# displayplank.net
KiCad netlist of a schematic drawn in EAGLE
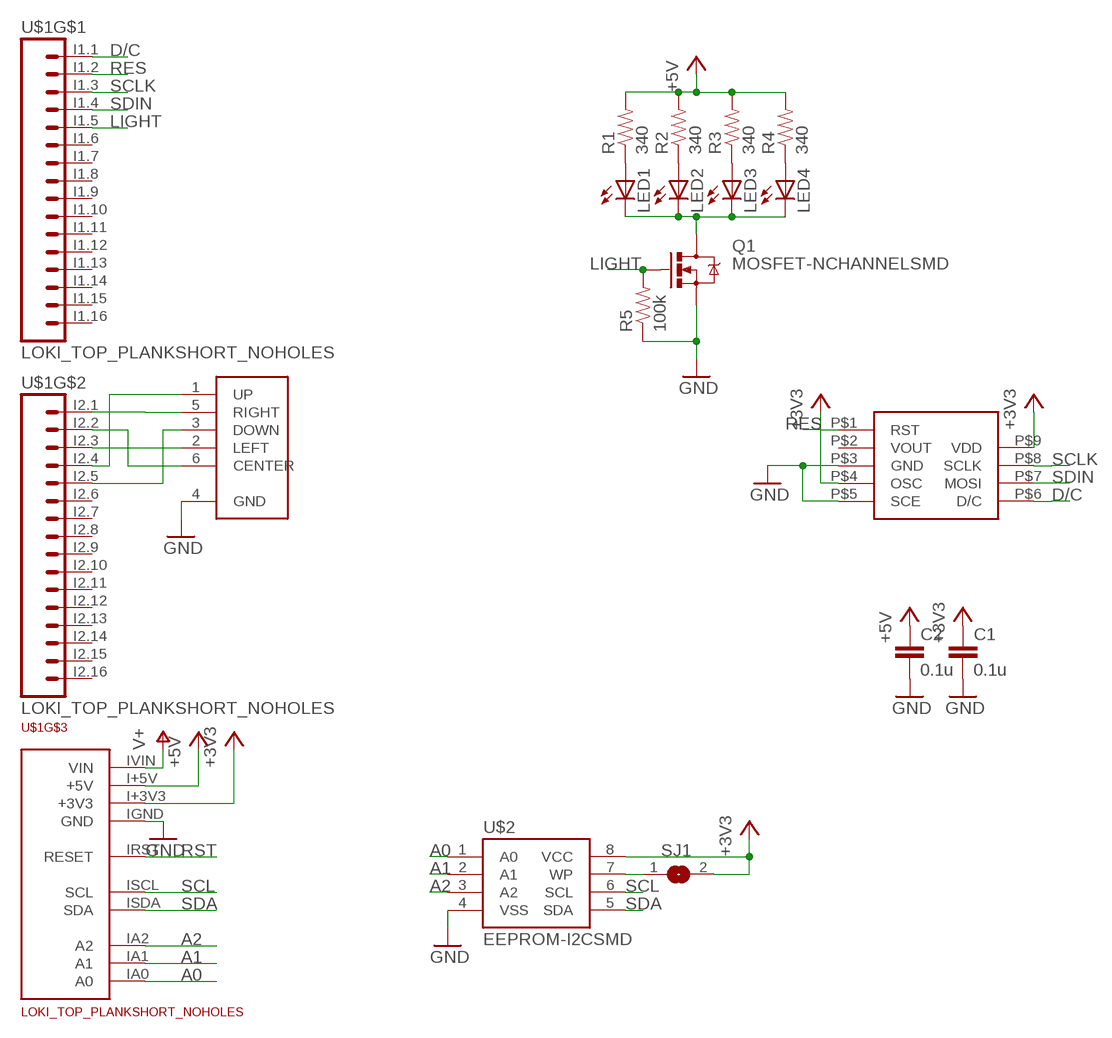
[diagram p0: schematic, sheet 1]

(export (version "E")
  (design (tool "Eeschema 10.0.6"))
  (components
    (comp (ref "C1")
      (value "0.1u")
      (footprint "eagle-import:0805")
      (libsource (lib "eagle-import") (part "CAP0805"))
    )
    (comp (ref "C2")
      (value "0.1u")
      (footprint "eagle-import:0805")
      (libsource (lib "eagle-import") (part "CAP0805"))
    )
    (comp (ref "LED1")
      (value "LEDSML0805")
      (footprint "eagle-import:SML0805")
      (libsource (lib "eagle-import") (part "LEDSML0805"))
    )
    (comp (ref "LED2")
      (value "LEDSML0805")
      (footprint "eagle-import:SML0805")
      (libsource (lib "eagle-import") (part "LEDSML0805"))
    )
    (comp (ref "LED3")
      (value "LEDSML0805")
      (footprint "eagle-import:SML0805")
      (libsource (lib "eagle-import") (part "LEDSML0805"))
    )
    (comp (ref "LED4")
      (value "LEDSML0805")
      (footprint "eagle-import:SML0805")
      (libsource (lib "eagle-import") (part "LEDSML0805"))
    )
    (comp (ref "Q1")
      (value "MOSFET-NCHANNELSMD")
      (footprint "eagle-import:SOT23-3")
      (libsource (lib "eagle-import") (part "MOSFET-NCHANNELSMD"))
    )
    (comp (ref "R1")
      (value "340")
      (footprint "eagle-import:0805")
      (libsource (lib "eagle-import") (part "RESISTOR0805-RES"))
    )
    (comp (ref "R2")
      (value "340")
      (footprint "eagle-import:0805")
      (libsource (lib "eagle-import") (part "RESISTOR0805-RES"))
    )
    (comp (ref "R3")
      (value "340")
      (footprint "eagle-import:0805")
      (libsource (lib "eagle-import") (part "RESISTOR0805-RES"))
    )
    (comp (ref "R4")
      (value "340")
      (footprint "eagle-import:0805")
      (libsource (lib "eagle-import") (part "RESISTOR0805-RES"))
    )
    (comp (ref "R5")
      (value "100k")
      (footprint "eagle-import:0805")
      (libsource (lib "eagle-import") (part "RESISTOR0805-RES"))
    )
    (comp (ref "SJ1") (value "SJ") (footprint "eagle-import:SJ") (libsource (lib "eagle-import") (part "SJ")))
    (comp (ref "U$1")
      (value "LOKI_TOP_PLANKSHORT_NOHOLES")
      (footprint "eagle-import:TOP_PLANK_SHORT_NOHOLES")
      (libsource (lib "eagle-import") (part "LOKI_TOP_PLANKSHORT_NOHOLES"))
    )
    (comp (ref "U$2")
      (value "EEPROM-I2CSMD")
      (footprint "eagle-import:SO08")
      (libsource (lib "eagle-import") (part "EEPROM-I2CSMD"))
    )
    (comp (ref "U$3")
      (value "JOYSTICK-10MM")
      (footprint "eagle-import:JOYSTICK-10MM")
      (libsource (lib "eagle-import") (part "JOYSTICK-10MM"))
    )
    (comp (ref "U$5")
      (value "5110-SCREEN")
      (footprint "eagle-import:5110-SCREEN")
      (libsource (lib "eagle-import") (part "5110-SCREEN"))
    )
  )
  (nets
    (net (code "1") (name "+3V3") (class "Default")
      (node (ref "C1") (pin "1") (pinfunction "1_1") (pintype "passive"))
      (node (ref "SJ1") (pin "2") (pinfunction "2_2") (pintype "passive"))
      (node (ref "U$1") (pin "I+3V3") (pinfunction "+3V3_I+3V3") (pintype "power_in"))
      (node (ref "U$2") (pin "8") (pinfunction "VCC_8") (pintype "power_in"))
      (node (ref "U$5") (pin "P$4") (pinfunction "OSC_P$4") (pintype "bidirectional"))
      (node (ref "U$5") (pin "P$9") (pinfunction "VDD_P$9") (pintype "bidirectional"))
    )
    (net (code "2") (name "+5V") (class "Default")
      (node (ref "C2") (pin "1") (pinfunction "1_1") (pintype "passive"))
      (node (ref "R1") (pin "2") (pinfunction "2_2") (pintype "passive"))
      (node (ref "R2") (pin "2") (pinfunction "2_2") (pintype "passive"))
      (node (ref "R3") (pin "2") (pinfunction "2_2") (pintype "passive"))
      (node (ref "R4") (pin "2") (pinfunction "2_2") (pintype "passive"))
      (node (ref "U$1") (pin "I+5V") (pinfunction "+5V_I+5V") (pintype "power_in"))
    )
    (net (code "3") (name "/A0") (class "Default")
      (node (ref "U$1") (pin "IA0") (pinfunction "A0_IA0") (pintype "output"))
      (node (ref "U$2") (pin "1") (pinfunction "A0_1") (pintype "bidirectional"))
    )
    (net (code "4") (name "/A1") (class "Default")
      (node (ref "U$1") (pin "IA1") (pinfunction "A1_IA1") (pintype "output"))
      (node (ref "U$2") (pin "2") (pinfunction "A1_2") (pintype "bidirectional"))
    )
    (net (code "5") (name "/A2") (class "Default")
      (node (ref "U$1") (pin "IA2") (pinfunction "A2_IA2") (pintype "output"))
      (node (ref "U$2") (pin "3") (pinfunction "A2_3") (pintype "bidirectional"))
    )
    (net (code "6") (name "/D{slash}C") (class "Default")
      (node (ref "U$1") (pin "I1.1") (pinfunction "1_I1.1") (pintype "passive"))
      (node (ref "U$5") (pin "P$6") (pinfunction "D/C_P$6") (pintype "bidirectional"))
    )
    (net (code "7") (name "/LIGHT") (class "Default")
      (node (ref "Q1") (pin "1") (pinfunction "G_1") (pintype "passive"))
      (node (ref "R5") (pin "2") (pinfunction "2_2") (pintype "passive"))
      (node (ref "U$1") (pin "I1.5") (pinfunction "5_I1.5") (pintype "passive"))
    )
    (net (code "8") (name "/RES") (class "Default")
      (node (ref "U$1") (pin "I1.2") (pinfunction "2_I1.2") (pintype "passive"))
      (node (ref "U$5") (pin "P$1") (pinfunction "RST_P$1") (pintype "bidirectional"))
    )
    (net (code "9") (name "/RST") (class "Default")
      (node (ref "U$1") (pin "IRST") (pinfunction "RESET_IRST") (pintype "input"))
    )
    (net (code "10") (name "/SCL") (class "Default")
      (node (ref "U$1") (pin "ISCL") (pinfunction "SCL_ISCL") (pintype "bidirectional"))
      (node (ref "U$2") (pin "6") (pinfunction "SCL_6") (pintype "bidirectional"))
    )
    (net (code "11") (name "/SCLK") (class "Default")
      (node (ref "U$1") (pin "I1.3") (pinfunction "3_I1.3") (pintype "passive"))
      (node (ref "U$5") (pin "P$8") (pinfunction "SCLK_P$8") (pintype "bidirectional"))
    )
    (net (code "12") (name "/SDA") (class "Default")
      (node (ref "U$1") (pin "ISDA") (pinfunction "SDA_ISDA") (pintype "bidirectional"))
      (node (ref "U$2") (pin "5") (pinfunction "SDA_5") (pintype "bidirectional"))
    )
    (net (code "13") (name "/SDIN") (class "Default")
      (node (ref "U$1") (pin "I1.4") (pinfunction "4_I1.4") (pintype "passive"))
      (node (ref "U$5") (pin "P$7") (pinfunction "MOSI_P$7") (pintype "bidirectional"))
    )
    (net (code "14") (name "GND") (class "Default")
      (node (ref "C1") (pin "2") (pinfunction "2_2") (pintype "passive"))
      (node (ref "C2") (pin "2") (pinfunction "2_2") (pintype "passive"))
      (node (ref "Q1") (pin "2") (pinfunction "S_2") (pintype "passive"))
      (node (ref "R5") (pin "1") (pinfunction "1_1") (pintype "passive"))
      (node (ref "U$1") (pin "IGND") (pinfunction "GND_IGND") (pintype "power_in"))
      (node (ref "U$2") (pin "4") (pinfunction "VSS_4") (pintype "power_in"))
      (node (ref "U$3") (pin "4") (pinfunction "GND_4") (pintype "passive"))
      (node (ref "U$5") (pin "P$3") (pinfunction "GND_P$3") (pintype "bidirectional"))
      (node (ref "U$5") (pin "P$5") (pinfunction "SCE_P$5") (pintype "bidirectional"))
    )
    (net (code "15") (name "Net-(LED1-PadA)") (class "Default")
      (node (ref "LED1") (pin "A") (pinfunction "A_A") (pintype "passive"))
      (node (ref "R1") (pin "1") (pinfunction "1_1") (pintype "passive"))
    )
    (net (code "16") (name "Net-(LED2-PadA)") (class "Default")
      (node (ref "LED2") (pin "A") (pinfunction "A_A") (pintype "passive"))
      (node (ref "R2") (pin "1") (pinfunction "1_1") (pintype "passive"))
    )
    (net (code "17") (name "Net-(LED3-PadA)") (class "Default")
      (node (ref "LED3") (pin "A") (pinfunction "A_A") (pintype "passive"))
      (node (ref "R3") (pin "1") (pinfunction "1_1") (pintype "passive"))
    )
    (net (code "18") (name "Net-(LED4-PadA)") (class "Default")
      (node (ref "LED4") (pin "A") (pinfunction "A_A") (pintype "passive"))
      (node (ref "R4") (pin "1") (pinfunction "1_1") (pintype "passive"))
    )
    (net (code "19") (name "Net-(Q1-D)") (class "Default")
      (node (ref "LED1") (pin "C") (pinfunction "C_C") (pintype "passive"))
      (node (ref "LED2") (pin "C") (pinfunction "C_C") (pintype "passive"))
      (node (ref "LED3") (pin "C") (pinfunction "C_C") (pintype "passive"))
      (node (ref "LED4") (pin "C") (pinfunction "C_C") (pintype "passive"))
      (node (ref "Q1") (pin "3") (pinfunction "D_3") (pintype "passive"))
    )
    (net (code "20") (name "Net-(U$1B-1)") (class "Default")
      (node (ref "U$1") (pin "I2.1") (pinfunction "1_I2.1") (pintype "passive"))
      (node (ref "U$3") (pin "5") (pinfunction "RIGHT_5") (pintype "passive"))
    )
    (net (code "21") (name "Net-(U$1B-2)") (class "Default")
      (node (ref "U$1") (pin "I2.2") (pinfunction "2_I2.2") (pintype "passive"))
      (node (ref "U$3") (pin "6") (pinfunction "CENTER_6") (pintype "passive"))
    )
    (net (code "22") (name "Net-(U$1B-3)") (class "Default")
      (node (ref "U$1") (pin "I2.3") (pinfunction "3_I2.3") (pintype "passive"))
      (node (ref "U$3") (pin "2") (pinfunction "LEFT_2") (pintype "passive"))
    )
    (net (code "23") (name "Net-(U$1B-4)") (class "Default")
      (node (ref "U$1") (pin "I2.4") (pinfunction "4_I2.4") (pintype "passive"))
      (node (ref "U$3") (pin "1") (pinfunction "UP_1") (pintype "passive"))
    )
    (net (code "24") (name "Net-(U$1B-5)") (class "Default")
      (node (ref "U$1") (pin "I2.5") (pinfunction "5_I2.5") (pintype "passive"))
      (node (ref "U$3") (pin "3") (pinfunction "DOWN_3") (pintype "passive"))
    )
    (net (code "25") (name "Net-(U$2-WP)") (class "Default")
      (node (ref "SJ1") (pin "1") (pinfunction "1_1") (pintype "passive"))
      (node (ref "U$2") (pin "7") (pinfunction "WP_7") (pintype "bidirectional"))
    )
    (net (code "26") (name "V+") (class "Default")
      (node (ref "U$1") (pin "IVIN") (pinfunction "VIN_IVIN") (pintype "power_in"))
    )
    (net (code "27") (name "unconnected-(U$1A-6-PadI1.6)") (class "Default")
      (node (ref "U$1") (pin "I1.6") (pinfunction "6_I1.6") (pintype "passive"))
    )
    (net (code "28") (name "unconnected-(U$1A-7-PadI1.7)") (class "Default")
      (node (ref "U$1") (pin "I1.7") (pinfunction "7_I1.7") (pintype "passive"))
    )
    (net (code "29") (name "unconnected-(U$1A-8-PadI1.8)") (class "Default")
      (node (ref "U$1") (pin "I1.8") (pinfunction "8_I1.8") (pintype "passive"))
    )
    (net (code "30") (name "unconnected-(U$1A-9-PadI1.9)") (class "Default")
      (node (ref "U$1") (pin "I1.9") (pinfunction "9_I1.9") (pintype "passive"))
    )
    (net (code "31") (name "unconnected-(U$1A-10-PadI1.10)") (class "Default")
      (node (ref "U$1") (pin "I1.10") (pinfunction "10_I1.10") (pintype "passive"))
    )
    (net (code "32") (name "unconnected-(U$1A-11-PadI1.11)") (class "Default")
      (node (ref "U$1") (pin "I1.11") (pinfunction "11_I1.11") (pintype "passive"))
    )
    (net (code "33") (name "unconnected-(U$1A-12-PadI1.12)") (class "Default")
      (node (ref "U$1") (pin "I1.12") (pinfunction "12_I1.12") (pintype "passive"))
    )
    (net (code "34") (name "unconnected-(U$1A-13-PadI1.13)") (class "Default")
      (node (ref "U$1") (pin "I1.13") (pinfunction "13_I1.13") (pintype "passive"))
    )
    (net (code "35") (name "unconnected-(U$1A-14-PadI1.14)") (class "Default")
      (node (ref "U$1") (pin "I1.14") (pinfunction "14_I1.14") (pintype "passive"))
    )
    (net (code "36") (name "unconnected-(U$1A-15-PadI1.15)") (class "Default")
      (node (ref "U$1") (pin "I1.15") (pinfunction "15_I1.15") (pintype "passive"))
    )
    (net (code "37") (name "unconnected-(U$1A-16-PadI1.16)") (class "Default")
      (node (ref "U$1") (pin "I1.16") (pinfunction "16_I1.16") (pintype "passive"))
    )
    (net (code "38") (name "unconnected-(U$1B-6-PadI2.6)") (class "Default")
      (node (ref "U$1") (pin "I2.6") (pinfunction "6_I2.6") (pintype "passive"))
    )
    (net (code "39") (name "unconnected-(U$1B-7-PadI2.7)") (class "Default")
      (node (ref "U$1") (pin "I2.7") (pinfunction "7_I2.7") (pintype "passive"))
    )
    (net (code "40") (name "unconnected-(U$1B-8-PadI2.8)") (class "Default")
      (node (ref "U$1") (pin "I2.8") (pinfunction "8_I2.8") (pintype "passive"))
    )
    (net (code "41") (name "unconnected-(U$1B-9-PadI2.9)") (class "Default")
      (node (ref "U$1") (pin "I2.9") (pinfunction "9_I2.9") (pintype "passive"))
    )
    (net (code "42") (name "unconnected-(U$1B-10-PadI2.10)") (class "Default")
      (node (ref "U$1") (pin "I2.10") (pinfunction "10_I2.10") (pintype "passive"))
    )
    (net (code "43") (name "unconnected-(U$1B-11-PadI2.11)") (class "Default")
      (node (ref "U$1") (pin "I2.11") (pinfunction "11_I2.11") (pintype "passive"))
    )
    (net (code "44") (name "unconnected-(U$1B-12-PadI2.12)") (class "Default")
      (node (ref "U$1") (pin "I2.12") (pinfunction "12_I2.12") (pintype "passive"))
    )
    (net (code "45") (name "unconnected-(U$1B-13-PadI2.13)") (class "Default")
      (node (ref "U$1") (pin "I2.13") (pinfunction "13_I2.13") (pintype "passive"))
    )
    (net (code "46") (name "unconnected-(U$1B-14-PadI2.14)") (class "Default")
      (node (ref "U$1") (pin "I2.14") (pinfunction "14_I2.14") (pintype "passive"))
    )
    (net (code "47") (name "unconnected-(U$1B-15-PadI2.15)") (class "Default")
      (node (ref "U$1") (pin "I2.15") (pinfunction "15_I2.15") (pintype "passive"))
    )
    (net (code "48") (name "unconnected-(U$1B-16-PadI2.16)") (class "Default")
      (node (ref "U$1") (pin "I2.16") (pinfunction "16_I2.16") (pintype "passive"))
    )
    (net (code "49") (name "unconnected-(U$5-VOUT-PadP$2)") (class "Default")
      (node (ref "U$5") (pin "P$2") (pinfunction "VOUT_P$2") (pintype "bidirectional"))
    )
  )
)
